# Nimb_Ring_2_0.net
KiCad netlist of a schematic drawn in Altium Designer
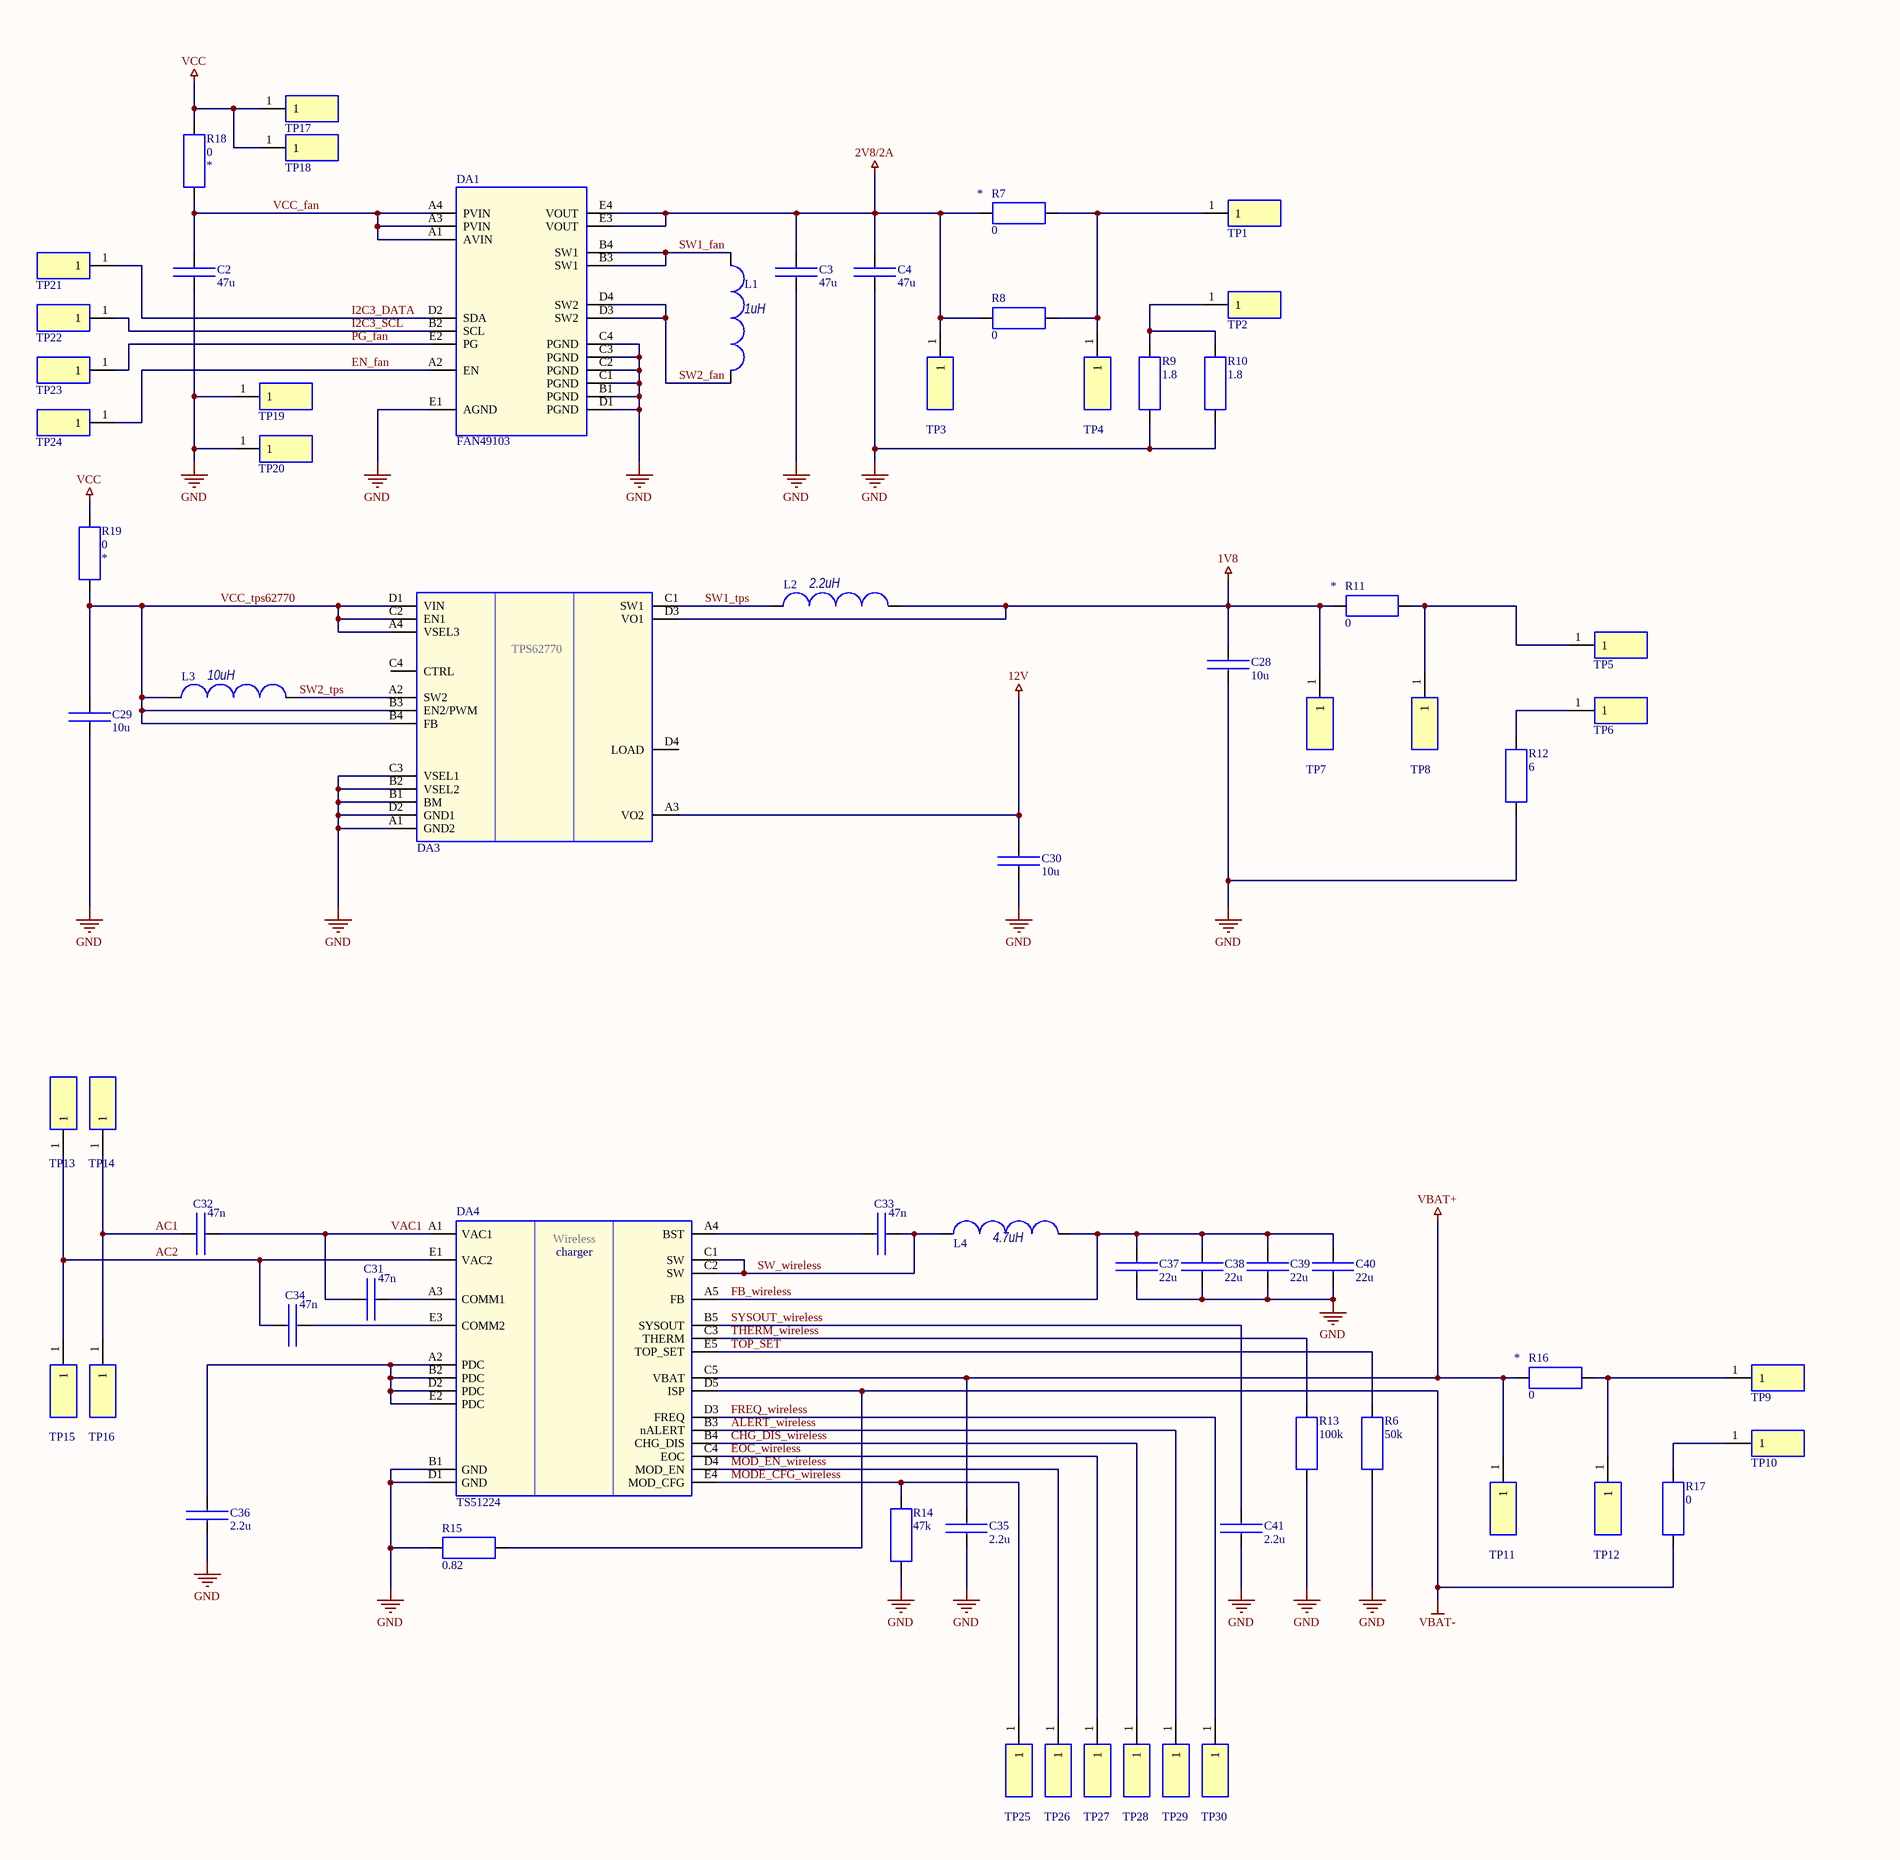
[diagram p0: Nimb_Ring_2_0.SchDoc, left]
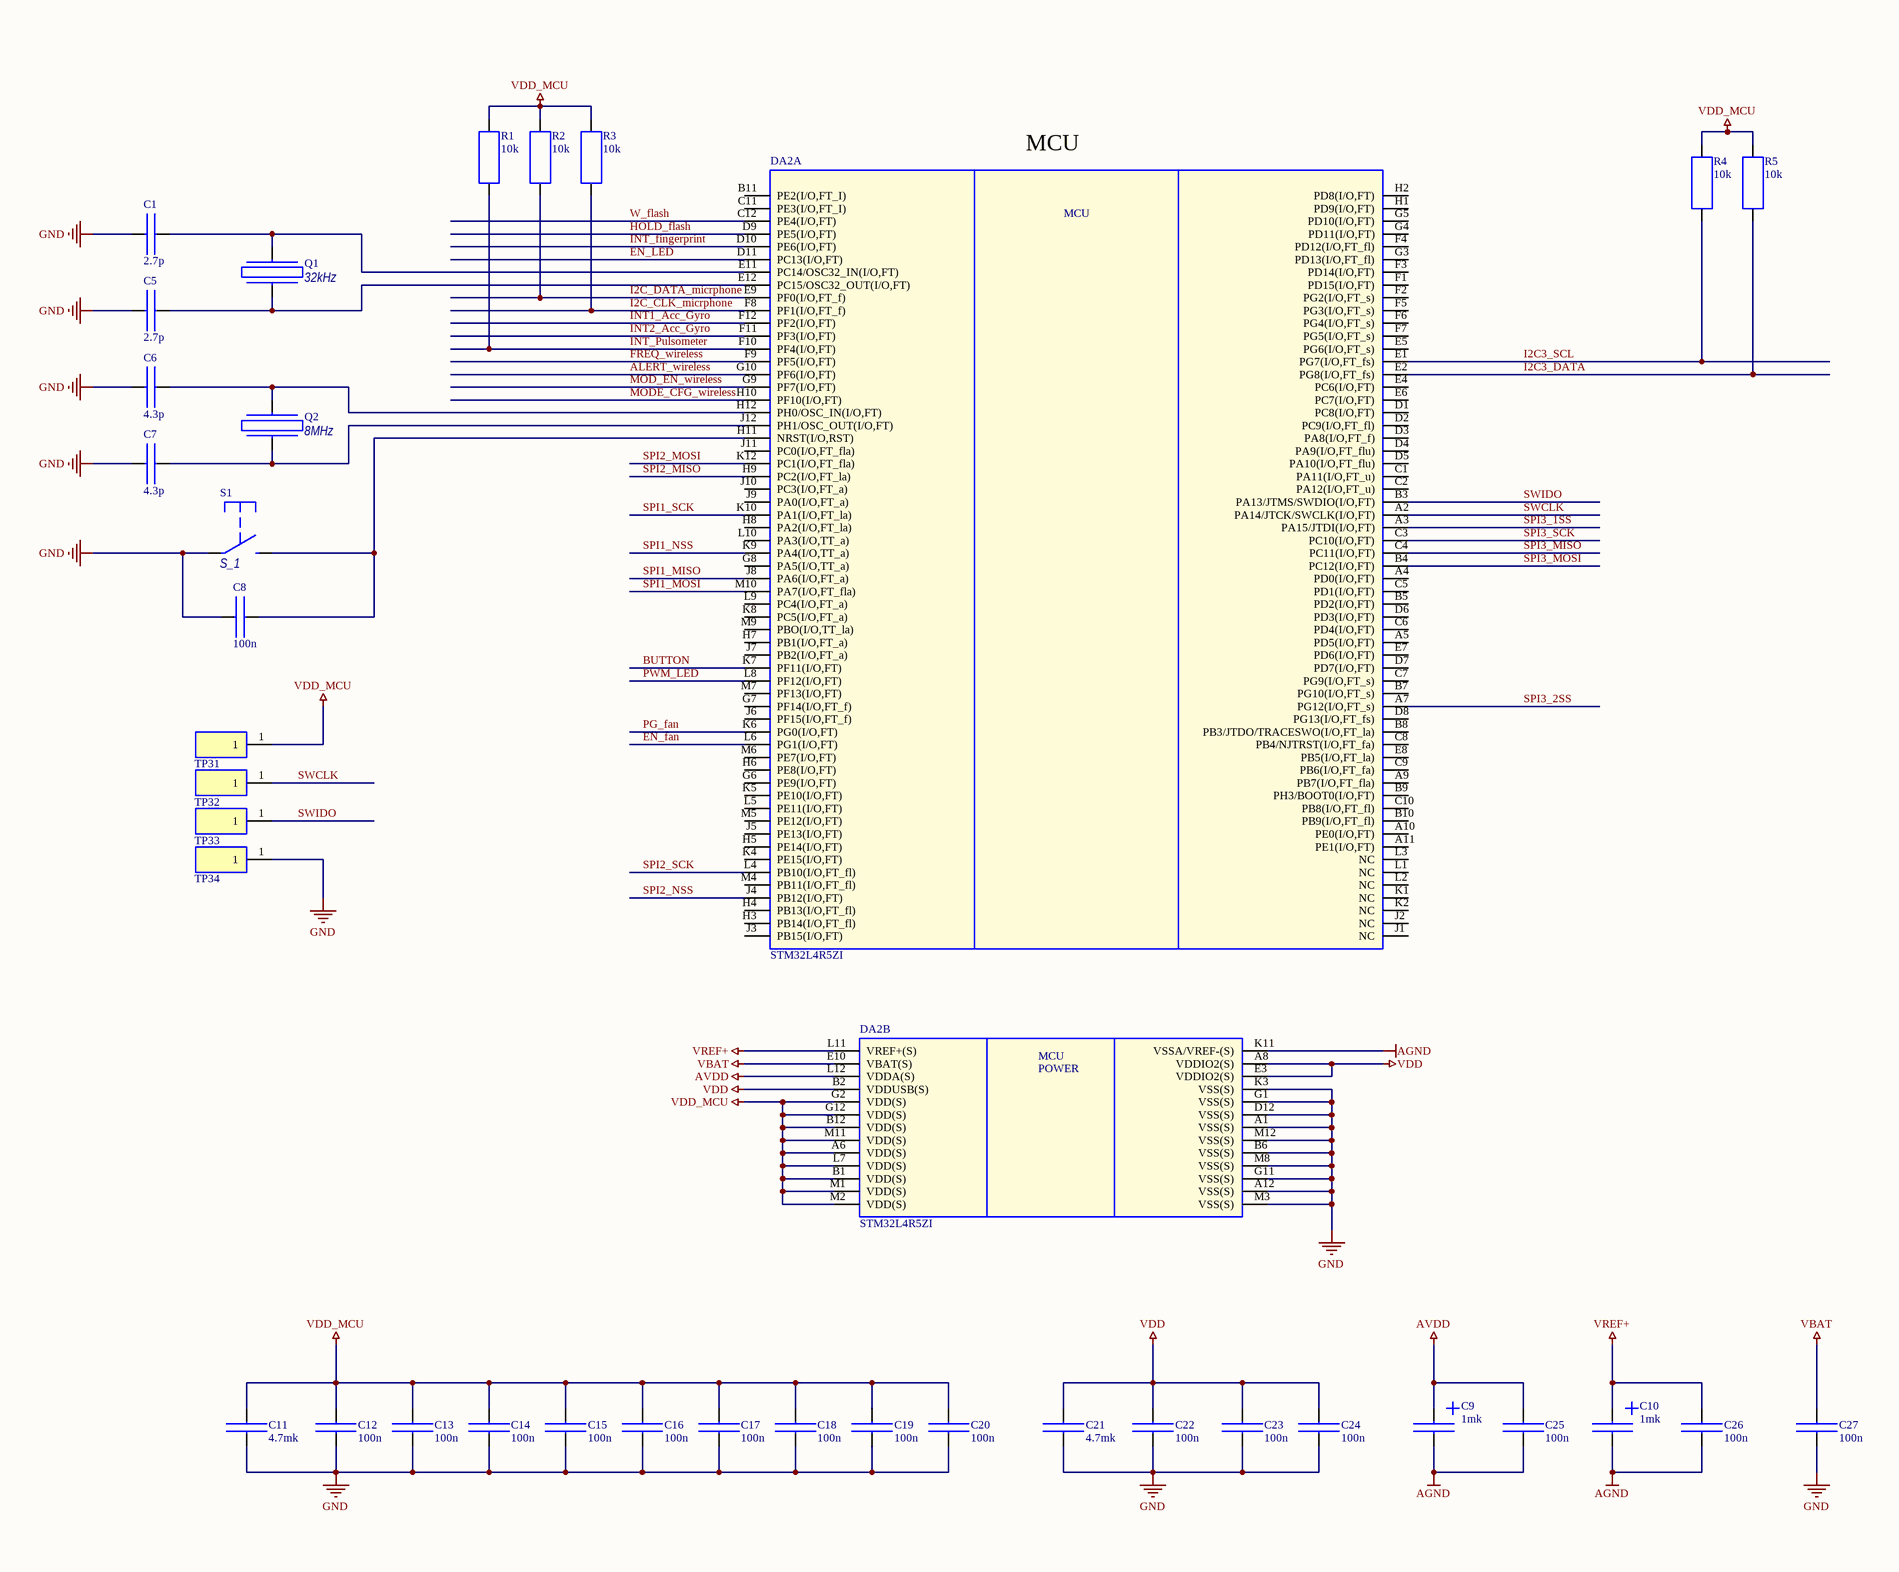
[diagram p1: Nimb_Ring_2_0.SchDoc, right]

(export (version "E")
  (design (tool "Eeschema 10.0.6"))
  (components
    (comp (ref "C1")
      (value "2.7p")
      (footprint "CAP_0201")
      (fields (field (name "MANUFACTURERPARTNUMBER") "GRM155R71C104KA88"))
      (libsource (lib "Altium_lib_Discrete") (part "C"))
    )
    (comp (ref "C2")
      (value "47u")
      (footprint "Cap0603")
      (description "CAP CER 47UF 6.3V X5R 0603")
      (fields (field (name "TOLERANCE") "20%") (field (name "MANUFACTURERPARTNUMBER") "GRM188R60J476ME15J"))
      (libsource (lib "Nimb_Ring") (part "C"))
    )
    (comp (ref "C3")
      (value "47u")
      (footprint "Cap0603")
      (description "CAP CER 47UF 6.3V X5R 0603")
      (fields (field (name "TOLERANCE") "20%") (field (name "MANUFACTURERPARTNUMBER") "GRM188R60J476ME15J"))
      (libsource (lib "Nimb_Ring") (part "C"))
    )
    (comp (ref "C4")
      (value "47u")
      (footprint "Cap0603")
      (description "CAP CER 47UF 6.3V X5R 0603")
      (fields (field (name "TOLERANCE") "20%") (field (name "MANUFACTURERPARTNUMBER") "GRM188R60J476ME15J"))
      (libsource (lib "Nimb_Ring") (part "C"))
    )
    (comp (ref "C5")
      (value "2.7p")
      (footprint "CAP_0201")
      (fields (field (name "MANUFACTURERPARTNUMBER") "GRM155R71C104KA88"))
      (libsource (lib "Altium_lib_Discrete") (part "C"))
    )
    (comp (ref "C6")
      (value "4.3p")
      (footprint "CAP_0201")
      (fields (field (name "MANUFACTURERPARTNUMBER") "GRM155R71C104KA88"))
      (libsource (lib "Altium_lib_Discrete") (part "C"))
    )
    (comp (ref "C7")
      (value "4.3p")
      (footprint "CAP_0201")
      (fields (field (name "MANUFACTURERPARTNUMBER") "GRM155R71C104KA88"))
      (libsource (lib "Altium_lib_Discrete") (part "C"))
    )
    (comp (ref "C8")
      (value "100n")
      (footprint "CAP_0201")
      (fields (field (name "MANUFACTURERPARTNUMBER") "GRM155R71C104KA88"))
      (libsource (lib "Altium_lib_Discrete") (part "C"))
    )
    (comp (ref "C9") (value "1mk") (footprint "CAP_0201") (libsource (lib "Nimb_Ring") (part "C_Polar")))
    (comp (ref "C10") (value "1mk") (footprint "CAP_0201") (libsource (lib "Nimb_Ring") (part "C_Polar")))
    (comp (ref "C11")
      (value "4.7mk")
      (footprint "CAP_0201")
      (libsource (lib "Altium_lib_Discrete") (part "C"))
    )
    (comp (ref "C12")
      (value "100n")
      (footprint "CAP_0201")
      (fields (field (name "MANUFACTURERPARTNUMBER") "GRM155R71C104KA88"))
      (libsource (lib "Altium_lib_Discrete") (part "C"))
    )
    (comp (ref "C13")
      (value "100n")
      (footprint "CAP_0201")
      (fields (field (name "MANUFACTURERPARTNUMBER") "GRM155R71C104KA88"))
      (libsource (lib "Altium_lib_Discrete") (part "C"))
    )
    (comp (ref "C14")
      (value "100n")
      (footprint "CAP_0201")
      (fields (field (name "MANUFACTURERPARTNUMBER") "GRM155R71C104KA88"))
      (libsource (lib "Altium_lib_Discrete") (part "C"))
    )
    (comp (ref "C15")
      (value "100n")
      (footprint "CAP_0201")
      (fields (field (name "MANUFACTURERPARTNUMBER") "GRM155R71C104KA88"))
      (libsource (lib "Altium_lib_Discrete") (part "C"))
    )
    (comp (ref "C16")
      (value "100n")
      (footprint "CAP_0201")
      (fields (field (name "MANUFACTURERPARTNUMBER") "GRM155R71C104KA88"))
      (libsource (lib "Altium_lib_Discrete") (part "C"))
    )
    (comp (ref "C17")
      (value "100n")
      (footprint "CAP_0201")
      (fields (field (name "MANUFACTURERPARTNUMBER") "GRM155R71C104KA88"))
      (libsource (lib "Altium_lib_Discrete") (part "C"))
    )
    (comp (ref "C18")
      (value "100n")
      (footprint "CAP_0201")
      (fields (field (name "MANUFACTURERPARTNUMBER") "GRM155R71C104KA88"))
      (libsource (lib "Altium_lib_Discrete") (part "C"))
    )
    (comp (ref "C19")
      (value "100n")
      (footprint "CAP_0201")
      (fields (field (name "MANUFACTURERPARTNUMBER") "GRM155R71C104KA88"))
      (libsource (lib "Altium_lib_Discrete") (part "C"))
    )
    (comp (ref "C20")
      (value "100n")
      (footprint "CAP_0201")
      (fields (field (name "MANUFACTURERPARTNUMBER") "GRM155R71C104KA88"))
      (libsource (lib "Altium_lib_Discrete") (part "C"))
    )
    (comp (ref "C21")
      (value "4.7mk")
      (footprint "CAP_0201")
      (libsource (lib "Altium_lib_Discrete") (part "C"))
    )
    (comp (ref "C22")
      (value "100n")
      (footprint "CAP_0201")
      (fields (field (name "MANUFACTURERPARTNUMBER") "GRM155R71C104KA88"))
      (libsource (lib "Altium_lib_Discrete") (part "C"))
    )
    (comp (ref "C23")
      (value "100n")
      (footprint "CAP_0201")
      (fields (field (name "MANUFACTURERPARTNUMBER") "GRM155R71C104KA88"))
      (libsource (lib "Altium_lib_Discrete") (part "C"))
    )
    (comp (ref "C24")
      (value "100n")
      (footprint "CAP_0201")
      (fields (field (name "MANUFACTURERPARTNUMBER") "GRM155R71C104KA88"))
      (libsource (lib "Altium_lib_Discrete") (part "C"))
    )
    (comp (ref "C25")
      (value "100n")
      (footprint "CAP_0201")
      (fields (field (name "MANUFACTURERPARTNUMBER") "GRM155R71C104KA88"))
      (libsource (lib "Altium_lib_Discrete") (part "C"))
    )
    (comp (ref "C26")
      (value "100n")
      (footprint "CAP_0201")
      (fields (field (name "MANUFACTURERPARTNUMBER") "GRM155R71C104KA88"))
      (libsource (lib "Altium_lib_Discrete") (part "C"))
    )
    (comp (ref "C27")
      (value "100n")
      (footprint "CAP_0201")
      (fields (field (name "MANUFACTURERPARTNUMBER") "GRM155R71C104KA88"))
      (libsource (lib "Altium_lib_Discrete") (part "C"))
    )
    (comp (ref "C28")
      (value "10u")
      (footprint "Cap0402")
      (description "CAP CER 10UF 6.3V X5R 0402")
      (fields (field (name "TOLERANCE") "20%") (field (name "MANUFACTURERPARTNUMBER") "GRM155R60J106ME44D"))
      (libsource (lib "Nimb_Ring") (part "C"))
    )
    (comp (ref "C29")
      (value "10u")
      (footprint "Cap0402")
      (description "CAP CER 10UF 6.3V X5R 0402")
      (fields (field (name "TOLERANCE") "20%") (field (name "MANUFACTURERPARTNUMBER") "GRM155R60J106ME44D"))
      (libsource (lib "Nimb_Ring") (part "C"))
    )
    (comp (ref "C30")
      (value "10u")
      (footprint "Cap0402")
      (description "CAP CER 10UF 6.3V X5R 0402")
      (fields (field (name "TOLERANCE") "20%") (field (name "MANUFACTURERPARTNUMBER") "GRM155R60J106ME44D"))
      (libsource (lib "Nimb_Ring") (part "C"))
    )
    (comp (ref "C31")
      (value "47n")
      (footprint "Cap0402")
      (description "CAP CER 47nF 50V X5R 0402")
      (fields (field (name "TOLERANCE") "10%") (field (name "MANUFACTURERPARTNUMBER") "GRM155R71H473KE14D"))
      (libsource (lib "Nimb_Ring") (part "C"))
    )
    (comp (ref "C32")
      (value "47n")
      (footprint "Cap0402")
      (description "CAP CER 47nF 50V X5R 0402")
      (fields (field (name "TOLERANCE") "10%") (field (name "MANUFACTURERPARTNUMBER") "GRM155R71H473KE14D"))
      (libsource (lib "Nimb_Ring") (part "C"))
    )
    (comp (ref "C33")
      (value "47n")
      (footprint "Cap0402")
      (description "CAP CER 47nF 10V X5R 0402")
      (fields (field (name "TOLERANCE") "10%") (field (name "MANUFACTURERPARTNUMBER") "GRM155R61A473KA01D"))
      (libsource (lib "Nimb_Ring") (part "C"))
    )
    (comp (ref "C34")
      (value "47n")
      (footprint "Cap0402")
      (description "CAP CER 47nF 50V X5R 0402")
      (fields (field (name "TOLERANCE") "10%") (field (name "MANUFACTURERPARTNUMBER") "GRM155R71H473KE14D"))
      (libsource (lib "Nimb_Ring") (part "C"))
    )
    (comp (ref "C35")
      (value "2.2u")
      (footprint "Cap0603")
      (description "CAP CER 2.2UF 10V X5R 0402")
      (fields (field (name "TOLERANCE") "10%") (field (name "MANUFACTURERPARTNUMBER") "GRM155R61A225KE95D"))
      (libsource (lib "Nimb_Ring") (part "C"))
    )
    (comp (ref "C36")
      (value "2.2u")
      (footprint "Cap0402")
      (description "CAP CER 2.2UF 25V X5R 0402")
      (fields (field (name "TOLERANCE") "10%") (field (name "MANUFACTURERPARTNUMBER") "GRM155R61E225KE11D"))
      (libsource (lib "Nimb_Ring") (part "C"))
    )
    (comp (ref "C37")
      (value "22u")
      (footprint "Cap0603")
      (description "CAP CER 22UF 10V X5R 0603")
      (fields (field (name "TOLERANCE") "15%") (field (name "MANUFACTURERPARTNUMBER") "ZRB18AR61A226ME01L"))
      (libsource (lib "Nimb_Ring") (part "C"))
    )
    (comp (ref "C38")
      (value "22u")
      (footprint "Cap0603")
      (description "CAP CER 22UF 10V X5R 0603")
      (fields (field (name "TOLERANCE") "15%") (field (name "MANUFACTURERPARTNUMBER") "ZRB18AR61A226ME01L"))
      (libsource (lib "Nimb_Ring") (part "C"))
    )
    (comp (ref "C39")
      (value "22u")
      (footprint "Cap0603")
      (description "CAP CER 22UF 10V X5R 0603")
      (fields (field (name "TOLERANCE") "15%") (field (name "MANUFACTURERPARTNUMBER") "ZRB18AR61A226ME01L"))
      (libsource (lib "Nimb_Ring") (part "C"))
    )
    (comp (ref "C40")
      (value "22u")
      (footprint "Cap0603")
      (description "CAP CER 22UF 10V X5R 0603")
      (fields (field (name "TOLERANCE") "15%") (field (name "MANUFACTURERPARTNUMBER") "ZRB18AR61A226ME01L"))
      (libsource (lib "Nimb_Ring") (part "C"))
    )
    (comp (ref "C41")
      (value "2.2u")
      (footprint "Cap0603")
      (description "CAP CER 2.2UF 10V X5R 0402")
      (fields (field (name "TOLERANCE") "10%") (field (name "MANUFACTURERPARTNUMBER") "GRM155R61A225KE95D"))
      (libsource (lib "Nimb_Ring") (part "C"))
    )
    (comp (ref "DA1")
      (value "FAN49103")
      (footprint "WLCSP20")
      (description "I2C Buck-Boost Regulator 2.5A")
      (fields (field (name "MANUFACTURER") "ON Semiconductor"))
      (libsource (lib "Nimb_Ring") (part "FAN49103"))
    )
    (comp (ref "DA2")
      (value "STM32L4R5ZI")
      (footprint "WLCSP144")
      (libsource (lib "Nimb_Ring") (part "STM32L4R5ZI"))
    )
    (comp (ref "DA3")
      (value "TPS62770")
      (footprint "DSBGA16")
      (description "Multi-Rail DC/DC Converter")
      (fields (field (name "MANUFACTURER") "Texas Instruments"))
      (libsource (lib "Nimb_Ring") (part "TPS62770"))
    )
    (comp (ref "DA4")
      (value "TS51224")
      (footprint "BGA_25 (5x5 ARRAY)")
      (description "IC RCVR CTLR WIRELESS 20-WLCSP")
      (fields (field (name "MANUFACTURER") "SEMTECH"))
      (libsource (lib "Nimb_Ring") (part "TS51224"))
    )
    (comp (ref "L1")
      (value "1uH")
      (footprint "Ind_0806")
      (description "FIXED IND 1UH 3.4A 0.048OHM")
      (fields (field (name "TOLERANCE") "20%") (field (name "MANUFACTURERPARTNUMBER") "DFE201612E1R0M"))
      (libsource (lib "Nimb_Ring") (part "L"))
    )
    (comp (ref "L2")
      (value "2.2uH")
      (footprint "IND_0806(2016metric)")
      (description "FIXED IND 2.2UH 1.2A 204mOHM")
      (fields (field (name "TOLERANCE") "20%") (field (name "MANUFACTURERPARTNUMBER") "1285AS-H-2R2M=P2"))
      (libsource (lib "Nimb_Ring") (part "L"))
    )
    (comp (ref "L3")
      (value "10uH")
      (footprint "IND_0806(2016metric)")
      (description "FIXED IND 10UH 225mA 1.2OHM")
      (fields (field (name "TOLERANCE") "10%") (field (name "MANUFACTURERPARTNUMBER") "LQH2MCN100K02L"))
      (libsource (lib "Nimb_Ring") (part "L"))
    )
    (comp (ref "L4")
      (value "4.7uH")
      (footprint "COIL-1008CS_V")
      (description "IND SMD 1008 4.7UH 1A 0.11OHM")
      (fields (field (name "TOLERANCE") "20%") (field (name "MANUFACTURERPARTNUMBER") "CVH252009-4R7M"))
      (libsource (lib "Nimb_Ring") (part "L"))
    )
    (comp (ref "Q1")
      (value "32kHz")
      (footprint "NX3215SA-32.768KHZ-EXS00A-MU00525")
      (libsource (lib "Altium_lib_Discrete") (part "Q_1"))
    )
    (comp (ref "Q2")
      (value "8MHz")
      (footprint "NDK-NX3225GD-8MHZ-STD-CRA-3_V")
      (libsource (lib "Altium_lib_Discrete") (part "Q_1"))
    )
    (comp (ref "R1") (value "10k") (footprint "RESC0402(1005)_L") (libsource (lib "Nimb_Ring") (part "R")))
    (comp (ref "R2") (value "10k") (footprint "RESC0402(1005)_L") (libsource (lib "Nimb_Ring") (part "R")))
    (comp (ref "R3") (value "10k") (footprint "RESC0402(1005)_L") (libsource (lib "Nimb_Ring") (part "R")))
    (comp (ref "R4") (value "10k") (footprint "RESC0402(1005)_L") (libsource (lib "Nimb_Ring") (part "R")))
    (comp (ref "R5") (value "10k") (footprint "RESC0402(1005)_L") (libsource (lib "Nimb_Ring") (part "R")))
    (comp (ref "R6")
      (value "50k")
      (footprint "RESC0402(1005)_L")
      (description "RES SMD 49.9kOHM 1% 62.5mW 0402")
      (fields (field (name "TOLERANCE") "1%") (field (name "MANUFACTURERPARTNUMBER") "RC0402FR-0749K9L"))
      (libsource (lib "Nimb_Ring") (part "R"))
    )
    (comp (ref "R7")
      (value "0")
      (footprint "RES2512(6332M)")
      (description "RES SMD 0 OHM 5% 1W 2512")
      (fields
        (field (name "TOLERANCE") "5%")
        (field (name "ПРИМЕЧАНИЕ") "*")
        (field (name "MANUFACTURERPARTNUMBER") "CR2512-J/-000ELF")
      )
      (libsource (lib "Nimb_Ring") (part "R"))
    )
    (comp (ref "R8")
      (value "0")
      (footprint "RES6.5-3.4X1.9")
      (description "Axial")
      (libsource (lib "Nimb_Ring") (part "R"))
    )
    (comp (ref "R9")
      (value "1.8")
      (footprint "RES2512(6332M)")
      (description "RES SMD 1.8OHM 5% 2W 2512")
      (fields
        (field (name "MANUFACTURERPARTNUMBER") "CRM2512-JW-1R8ELF")
        (field (name "MANUFACTURER") "Bourns")
      )
      (libsource (lib "Nimb_Ring") (part "R"))
    )
    (comp (ref "R10")
      (value "1.8")
      (footprint "RES6.5-3.4X1.9")
      (description "Axial")
      (libsource (lib "Nimb_Ring") (part "R"))
    )
    (comp (ref "R11")
      (value "0")
      (footprint "RES2512(6332M)")
      (description "RES SMD 0 OHM 5% 1W 2512")
      (fields
        (field (name "TOLERANCE") "5%")
        (field (name "ПРИМЕЧАНИЕ") "*")
        (field (name "MANUFACTURERPARTNUMBER") "CR2512-J/-000ELF")
      )
      (libsource (lib "Nimb_Ring") (part "R"))
    )
    (comp (ref "R12")
      (value "6")
      (footprint "RES2512(6332M)")
      (description "RES SMD 6OHM 5% 1W 2512")
      (fields (field (name "TOLERANCE") "1%") (field (name "MANUFACTURERPARTNUMBER") "RC2512FK-076R04L"))
      (libsource (lib "Nimb_Ring") (part "R"))
    )
    (comp (ref "R13")
      (value "100k")
      (footprint "RESC0402(1005)_L")
      (description "RES SMD 100kOHM 5% 62.5mW 0402")
      (fields (field (name "TOLERANCE") "5%") (field (name "MANUFACTURERPARTNUMBER") "RC0402JR-07100KL"))
      (libsource (lib "Nimb_Ring") (part "R"))
    )
    (comp (ref "R14")
      (value "47k")
      (footprint "RESC0402(1005)_L")
      (description "RES SMD 47kOHM 5% 62.5mW 0402")
      (fields (field (name "TOLERANCE") "5%") (field (name "MANUFACTURERPARTNUMBER") "RC0402JR-0747KL"))
      (libsource (lib "Nimb_Ring") (part "R"))
    )
    (comp (ref "R15")
      (value "0.82")
      (footprint "RES0603(1608M)")
      (description "RES SMD 0OHM 5% 1A 0603")
      (fields (field (name "TOLERANCE") "5%") (field (name "MANUFACTURERPARTNUMBER") "CRCW0603R820FSEABL"))
      (libsource (lib "Nimb_Ring") (part "R"))
    )
    (comp (ref "R16")
      (value "0")
      (footprint "RES2512(6332M)")
      (description "RES SMD 0 OHM 5% 1W 2512")
      (fields
        (field (name "TOLERANCE") "5%")
        (field (name "ПРИМЕЧАНИЕ") "*")
        (field (name "MANUFACTURERPARTNUMBER") "CR2512-J/-000ELF")
      )
      (libsource (lib "Nimb_Ring") (part "R"))
    )
    (comp (ref "R17") (value "0") (footprint "RES2512(6332M)") (libsource (lib "Nimb_Ring") (part "R")))
    (comp (ref "R18")
      (value "0")
      (footprint "RES2512(6332M)")
      (description "RES SMD 0 OHM 5% 1W 2512")
      (fields
        (field (name "TOLERANCE") "5%")
        (field (name "ПРИМЕЧАНИЕ") "*")
        (field (name "MANUFACTURERPARTNUMBER") "CR2512-J/-000ELF")
      )
      (libsource (lib "Nimb_Ring") (part "R"))
    )
    (comp (ref "R19")
      (value "0")
      (footprint "RES2512(6332M)")
      (description "RES SMD 0 OHM 5% 1W 2512")
      (fields
        (field (name "TOLERANCE") "5%")
        (field (name "ПРИМЕЧАНИЕ") "*")
        (field (name "MANUFACTURERPARTNUMBER") "CR2512-J/-000ELF")
      )
      (libsource (lib "Nimb_Ring") (part "R"))
    )
    (comp (ref "S1")
      (value "S_1")
      (footprint "BOUR-7914G-1-000E_V")
      (libsource (lib "Nimb_Ring") (part "S_1"))
    )
    (comp (ref "TP1")
      (value "Test_Pad")
      (footprint "TEST_PAD_Button")
      (libsource (lib "") (part "Test_Pad_1"))
    )
    (comp (ref "TP2")
      (value "Test_Pad")
      (footprint "TEST_PAD_Button")
      (libsource (lib "") (part "Test_Pad_1"))
    )
    (comp (ref "TP3") (value "Test_Pad") (footprint "Test_Pad_PLS1") (libsource (lib "") (part "Test_Pad_2")))
    (comp (ref "TP4") (value "Test_Pad") (footprint "Test_Pad_PLS1") (libsource (lib "") (part "Test_Pad_2")))
    (comp (ref "TP5")
      (value "Test_Pad")
      (footprint "TEST_PAD_Button")
      (libsource (lib "") (part "Test_Pad_1"))
    )
    (comp (ref "TP6")
      (value "Test_Pad")
      (footprint "TEST_PAD_Button")
      (libsource (lib "") (part "Test_Pad_1"))
    )
    (comp (ref "TP7") (value "Test_Pad") (footprint "Test_Pad_PLS1") (libsource (lib "") (part "Test_Pad_2")))
    (comp (ref "TP8") (value "Test_Pad") (footprint "Test_Pad_PLS1") (libsource (lib "") (part "Test_Pad_2")))
    (comp (ref "TP9")
      (value "Test_Pad")
      (footprint "TEST_PAD_Button")
      (libsource (lib "") (part "Test_Pad_1"))
    )
    (comp (ref "TP10")
      (value "Test_Pad")
      (footprint "TEST_PAD_Button")
      (libsource (lib "") (part "Test_Pad_1"))
    )
    (comp (ref "TP11")
      (value "Test_Pad")
      (footprint "Test_Pad_PLS1")
      (libsource (lib "") (part "Test_Pad_2"))
    )
    (comp (ref "TP12")
      (value "Test_Pad")
      (footprint "Test_Pad_PLS1")
      (libsource (lib "") (part "Test_Pad_2"))
    )
    (comp (ref "TP13")
      (value "Test_Pad")
      (footprint "Test_Pad_PLS1")
      (libsource (lib "") (part "Test_Pad_3"))
    )
    (comp (ref "TP14")
      (value "Test_Pad")
      (footprint "Test_Pad_PLS1")
      (libsource (lib "") (part "Test_Pad_3"))
    )
    (comp (ref "TP15")
      (value "Test_Pad")
      (footprint "TEST_PAD_Button")
      (libsource (lib "") (part "Test_Pad_2"))
    )
    (comp (ref "TP16")
      (value "Test_Pad")
      (footprint "TEST_PAD_Button")
      (libsource (lib "") (part "Test_Pad_2"))
    )
    (comp (ref "TP17")
      (value "Test_Pad")
      (footprint "TEST_PAD_Button")
      (libsource (lib "") (part "Test_Pad_1"))
    )
    (comp (ref "TP18")
      (value "Test_Pad")
      (footprint "Test_Pad_PLS1")
      (libsource (lib "") (part "Test_Pad_1"))
    )
    (comp (ref "TP19")
      (value "Test_Pad")
      (footprint "TEST_PAD_Button")
      (libsource (lib "") (part "Test_Pad_1"))
    )
    (comp (ref "TP20")
      (value "Test_Pad")
      (footprint "Test_Pad_PLS1")
      (libsource (lib "") (part "Test_Pad_1"))
    )
    (comp (ref "TP21")
      (value "Test_Pad")
      (footprint "Test_Pad_PLS1")
      (libsource (lib "Nimb_Ring") (part "Test_Pad"))
    )
    (comp (ref "TP22")
      (value "Test_Pad")
      (footprint "Test_Pad_PLS1")
      (libsource (lib "Nimb_Ring") (part "Test_Pad"))
    )
    (comp (ref "TP23")
      (value "Test_Pad")
      (footprint "Test_Pad_PLS1")
      (libsource (lib "Nimb_Ring") (part "Test_Pad"))
    )
    (comp (ref "TP24")
      (value "Test_Pad")
      (footprint "Test_Pad_PLS1")
      (libsource (lib "Nimb_Ring") (part "Test_Pad"))
    )
    (comp (ref "TP25")
      (value "Test_Pad")
      (footprint "Test_Pad_PLS1")
      (libsource (lib "") (part "Test_Pad_2"))
    )
    (comp (ref "TP26")
      (value "Test_Pad")
      (footprint "Test_Pad_PLS1")
      (libsource (lib "") (part "Test_Pad_2"))
    )
    (comp (ref "TP27")
      (value "Test_Pad")
      (footprint "Test_Pad_PLS1")
      (libsource (lib "") (part "Test_Pad_2"))
    )
    (comp (ref "TP28")
      (value "Test_Pad")
      (footprint "Test_Pad_PLS1")
      (libsource (lib "") (part "Test_Pad_2"))
    )
    (comp (ref "TP29")
      (value "Test_Pad")
      (footprint "Test_Pad_PLS1")
      (libsource (lib "") (part "Test_Pad_2"))
    )
    (comp (ref "TP30")
      (value "Test_Pad")
      (footprint "Test_Pad_PLS1")
      (libsource (lib "") (part "Test_Pad_2"))
    )
    (comp (ref "TP31")
      (value "Test_Pad")
      (footprint "Test_Pad_PLS1")
      (libsource (lib "Nimb_Ring") (part "Test_Pad"))
    )
    (comp (ref "TP32")
      (value "Test_Pad")
      (footprint "Test_Pad_PLS1")
      (libsource (lib "Nimb_Ring") (part "Test_Pad"))
    )
    (comp (ref "TP33")
      (value "Test_Pad")
      (footprint "Test_Pad_PLS1")
      (libsource (lib "Nimb_Ring") (part "Test_Pad"))
    )
    (comp (ref "TP34")
      (value "Test_Pad")
      (footprint "Test_Pad_PLS1")
      (libsource (lib "Nimb_Ring") (part "Test_Pad"))
    )
  )
  (nets
    (net (code "1") (name "/AC1") (class "Default")
      (node (ref "C32") (pin "1") (pintype "passive"))
      (node (ref "TP14") (pin "1") (pinfunction "1_1") (pintype "passive"))
      (node (ref "TP16") (pin "1") (pinfunction "1_1") (pintype "passive"))
    )
    (net (code "2") (name "/AC2") (class "Default")
      (node (ref "C34") (pin "1") (pintype "passive"))
      (node (ref "DA4") (pin "E1") (pinfunction "VAC2_E1") (pintype "passive"))
      (node (ref "TP13") (pin "1") (pinfunction "1_1") (pintype "passive"))
      (node (ref "TP15") (pin "1") (pinfunction "1_1") (pintype "passive"))
    )
    (net (code "3") (name "/ALERT_wireless") (class "Default")
      (node (ref "DA2") (pin "G10") (pinfunction "PF6(I/O,FT)_G10") (pintype "passive"))
      (node (ref "DA4") (pin "B3") (pinfunction "nALERT_B3") (pintype "passive"))
      (node (ref "TP29") (pin "1") (pinfunction "1_1") (pintype "passive"))
    )
    (net (code "4") (name "/BUTTON") (class "Default")
      (node (ref "DA2") (pin "K7") (pinfunction "PF11(I/O,FT)_K7") (pintype "passive"))
    )
    (net (code "5") (name "/CHG_DIS_wireless") (class "Default")
      (node (ref "DA4") (pin "B4") (pinfunction "CHG_DIS_B4") (pintype "passive"))
      (node (ref "TP28") (pin "1") (pinfunction "1_1") (pintype "passive"))
    )
    (net (code "6") (name "/EN_LED") (class "Default")
      (node (ref "DA2") (pin "D11") (pinfunction "PC13(I/O,FT)_D11") (pintype "passive"))
    )
    (net (code "7") (name "/EN_fan") (class "Default")
      (node (ref "DA1") (pin "A2") (pinfunction "EN_A2") (pintype "passive"))
      (node (ref "DA2") (pin "L6") (pinfunction "PG1(I/O,FT)_L6") (pintype "passive"))
      (node (ref "TP24") (pin "1") (pinfunction "1_1") (pintype "passive"))
    )
    (net (code "8") (name "/EOC_wireless") (class "Default")
      (node (ref "DA4") (pin "C4") (pinfunction "EOC_C4") (pintype "passive"))
      (node (ref "TP27") (pin "1") (pinfunction "1_1") (pintype "passive"))
    )
    (net (code "9") (name "/FB_wireless") (class "Default")
      (node (ref "C37") (pin "1") (pintype "passive"))
      (node (ref "C38") (pin "1") (pintype "passive"))
      (node (ref "C39") (pin "1") (pintype "passive"))
      (node (ref "C40") (pin "1") (pintype "passive"))
      (node (ref "DA4") (pin "A5") (pinfunction "FB_A5") (pintype "passive"))
      (node (ref "L4") (pin "2") (pintype "passive"))
    )
    (net (code "10") (name "/FREQ_wireless") (class "Default")
      (node (ref "DA2") (pin "F9") (pinfunction "PF5(I/O,FT)_F9") (pintype "passive"))
      (node (ref "DA4") (pin "D3") (pinfunction "FREQ_D3") (pintype "passive"))
      (node (ref "TP30") (pin "1") (pinfunction "1_1") (pintype "passive"))
    )
    (net (code "11") (name "/HOLD_flash") (class "Default")
      (node (ref "DA2") (pin "D9") (pinfunction "PE5(I/O,FT)_D9") (pintype "passive"))
    )
    (net (code "12") (name "/I2C3_DATA") (class "Default")
      (node (ref "DA1") (pin "D2") (pinfunction "SDA_D2") (pintype "passive"))
      (node (ref "DA2") (pin "E2") (pinfunction "PG8(I/O,FT_fs)_E2") (pintype "passive"))
      (node (ref "R5") (pin "1") (pintype "passive"))
      (node (ref "TP21") (pin "1") (pinfunction "1_1") (pintype "passive"))
    )
    (net (code "13") (name "/I2C3_SCL") (class "Default")
      (node (ref "DA1") (pin "B2") (pinfunction "SCL_B2") (pintype "passive"))
      (node (ref "DA2") (pin "E1") (pinfunction "PG7(I/O,FT_fs)_E1") (pintype "passive"))
      (node (ref "R4") (pin "1") (pintype "passive"))
      (node (ref "TP22") (pin "1") (pinfunction "1_1") (pintype "passive"))
    )
    (net (code "14") (name "/I2C_CLK_micrphone") (class "Default")
      (node (ref "DA2") (pin "F8") (pinfunction "PF1(I/O,FT_f)_F8") (pintype "passive"))
      (node (ref "R3") (pin "1") (pintype "passive"))
    )
    (net (code "15") (name "/I2C_DATA_micrphone") (class "Default")
      (node (ref "DA2") (pin "E9") (pinfunction "PF0(I/O,FT_f)_E9") (pintype "passive"))
      (node (ref "R2") (pin "1") (pintype "passive"))
    )
    (net (code "16") (name "/INT1_Acc_Gyro") (class "Default")
      (node (ref "DA2") (pin "F12") (pinfunction "PF2(I/O,FT)_F12") (pintype "passive"))
    )
    (net (code "17") (name "/INT2_Acc_Gyro") (class "Default")
      (node (ref "DA2") (pin "F11") (pinfunction "PF3(I/O,FT)_F11") (pintype "passive"))
    )
    (net (code "18") (name "/INT_Pulsometer") (class "Default")
      (node (ref "DA2") (pin "F10") (pinfunction "PF4(I/O,FT)_F10") (pintype "passive"))
      (node (ref "R1") (pin "1") (pintype "passive"))
    )
    (net (code "19") (name "/INT_fingerprint") (class "Default")
      (node (ref "DA2") (pin "D10") (pinfunction "PE6(I/O,FT)_D10") (pintype "passive"))
    )
    (net (code "20") (name "/MODE_CFG_wireless") (class "Default")
      (node (ref "DA2") (pin "H10") (pinfunction "PF10(I/O,FT)_H10") (pintype "passive"))
      (node (ref "DA4") (pin "E4") (pinfunction "MOD_CFG_E4") (pintype "passive"))
      (node (ref "R14") (pin "2") (pintype "passive"))
      (node (ref "TP25") (pin "1") (pinfunction "1_1") (pintype "passive"))
    )
    (net (code "21") (name "/MOD_EN_wireless") (class "Default")
      (node (ref "DA2") (pin "G9") (pinfunction "PF7(I/O,FT)_G9") (pintype "passive"))
      (node (ref "DA4") (pin "D4") (pinfunction "MOD_EN_D4") (pintype "passive"))
      (node (ref "TP26") (pin "1") (pinfunction "1_1") (pintype "passive"))
    )
    (net (code "22") (name "/PG_fan") (class "Default")
      (node (ref "DA1") (pin "E2") (pinfunction "PG_E2") (pintype "passive"))
      (node (ref "DA2") (pin "K6") (pinfunction "PG0(I/O,FT)_K6") (pintype "passive"))
      (node (ref "TP23") (pin "1") (pinfunction "1_1") (pintype "passive"))
    )
    (net (code "23") (name "/PWM_LED") (class "Default")
      (node (ref "DA2") (pin "L8") (pinfunction "PF12(I/O,FT)_L8") (pintype "passive"))
    )
    (net (code "24") (name "/SPI1_MISO") (class "Default")
      (node (ref "DA2") (pin "J8") (pinfunction "PA6(I/O,FT_a)_J8") (pintype "passive"))
    )
    (net (code "25") (name "/SPI1_MOSI") (class "Default")
      (node (ref "DA2") (pin "M10") (pinfunction "PA7(I/O,FT_fla)_M10") (pintype "passive"))
    )
    (net (code "26") (name "/SPI1_NSS") (class "Default")
      (node (ref "DA2") (pin "K9") (pinfunction "PA4(I/O,TT_a)_K9") (pintype "passive"))
    )
    (net (code "27") (name "/SPI1_SCK") (class "Default")
      (node (ref "DA2") (pin "K10") (pinfunction "PA1(I/O,FT_la)_K10") (pintype "passive"))
    )
    (net (code "28") (name "/SPI2_MISO") (class "Default")
      (node (ref "DA2") (pin "H9") (pinfunction "PC2(I/O,FT_la)_H9") (pintype "passive"))
    )
    (net (code "29") (name "/SPI2_MOSI") (class "Default")
      (node (ref "DA2") (pin "K12") (pinfunction "PC1(I/O,FT_fla)_K12") (pintype "passive"))
    )
    (net (code "30") (name "/SPI2_NSS") (class "Default")
      (node (ref "DA2") (pin "J4") (pinfunction "PB12(I/O,FT)_J4") (pintype "passive"))
    )
    (net (code "31") (name "/SPI2_SCK") (class "Default")
      (node (ref "DA2") (pin "L4") (pinfunction "PB10(I/O,FT_fl)_L4") (pintype "passive"))
    )
    (net (code "32") (name "/SPI3_1SS") (class "Default")
      (node (ref "DA2") (pin "A3") (pinfunction "PA15/JTDI(I/O,FT)_A3") (pintype "passive"))
    )
    (net (code "33") (name "/SPI3_2SS") (class "Default")
      (node (ref "DA2") (pin "A7") (pinfunction "PG12(I/O,FT_s)_A7") (pintype "passive"))
    )
    (net (code "34") (name "/SPI3_MISO") (class "Default")
      (node (ref "DA2") (pin "C4") (pinfunction "PC11(I/O,FT)_C4") (pintype "passive"))
    )
    (net (code "35") (name "/SPI3_MOSI") (class "Default")
      (node (ref "DA2") (pin "B4") (pinfunction "PC12(I/O,FT)_B4") (pintype "passive"))
    )
    (net (code "36") (name "/SPI3_SCK") (class "Default")
      (node (ref "DA2") (pin "C3") (pinfunction "PC10(I/O,FT)_C3") (pintype "passive"))
    )
    (net (code "37") (name "/SW1_fan") (class "Default")
      (node (ref "DA1") (pin "B3") (pinfunction "SW1_B3") (pintype "passive"))
      (node (ref "DA1") (pin "B4") (pinfunction "SW1_B4") (pintype "passive"))
      (node (ref "L1") (pin "1") (pintype "passive"))
    )
    (net (code "38") (name "/SW1_tps") (class "Default")
      (node (ref "DA3") (pin "C1") (pinfunction "SW1_C1") (pintype "passive"))
      (node (ref "L2") (pin "1") (pintype "passive"))
    )
    (net (code "39") (name "/SW2_fan") (class "Default")
      (node (ref "DA1") (pin "D3") (pinfunction "SW2_D3") (pintype "passive"))
      (node (ref "DA1") (pin "D4") (pinfunction "SW2_D4") (pintype "passive"))
      (node (ref "L1") (pin "2") (pintype "passive"))
    )
    (net (code "40") (name "/SW2_tps") (class "Default")
      (node (ref "DA3") (pin "A2") (pinfunction "SW2_A2") (pintype "passive"))
      (node (ref "L3") (pin "2") (pintype "passive"))
    )
    (net (code "41") (name "/SWCLK") (class "Default")
      (node (ref "DA2") (pin "A2") (pinfunction "PA14/JTCK/SWCLK(I/O,FT)_A2") (pintype "passive"))
      (node (ref "TP32") (pin "1") (pinfunction "1_1") (pintype "passive"))
    )
    (net (code "42") (name "/SWIDO") (class "Default")
      (node (ref "DA2") (pin "B3") (pinfunction "PA13/JTMS/SWDIO(I/O,FT)_B3") (pintype "passive"))
      (node (ref "TP33") (pin "1") (pinfunction "1_1") (pintype "passive"))
    )
    (net (code "43") (name "/SW_wireless") (class "Default")
      (node (ref "C33") (pin "1") (pintype "passive"))
      (node (ref "DA4") (pin "C1") (pinfunction "SW_C1") (pintype "passive"))
      (node (ref "DA4") (pin "C2") (pinfunction "SW_C2") (pintype "passive"))
      (node (ref "L4") (pin "1") (pintype "passive"))
    )
    (net (code "44") (name "/SYSOUT_wireless") (class "Default")
      (node (ref "C41") (pin "1") (pintype "passive"))
      (node (ref "DA4") (pin "B5") (pinfunction "SYSOUT_B5") (pintype "passive"))
    )
    (net (code "45") (name "/THERM_wireless") (class "Default")
      (node (ref "DA4") (pin "C3") (pinfunction "THERM_C3") (pintype "passive"))
      (node (ref "R13") (pin "2") (pintype "passive"))
    )
    (net (code "46") (name "/TOP_SET") (class "Default")
      (node (ref "DA4") (pin "E5") (pinfunction "TOP_SET_E5") (pintype "passive"))
      (node (ref "R6") (pin "2") (pintype "passive"))
    )
    (net (code "47") (name "/VAC1") (class "Default")
      (node (ref "C31") (pin "1") (pintype "passive"))
      (node (ref "C32") (pin "2") (pintype "passive"))
      (node (ref "DA4") (pin "A1") (pinfunction "VAC1_A1") (pintype "passive"))
    )
    (net (code "48") (name "/VCC_fan") (class "Default")
      (node (ref "C2") (pin "2") (pintype "passive"))
      (node (ref "DA1") (pin "A1") (pinfunction "AVIN_A1") (pintype "passive"))
      (node (ref "DA1") (pin "A3") (pinfunction "PVIN_A3") (pintype "passive"))
      (node (ref "DA1") (pin "A4") (pinfunction "PVIN_A4") (pintype "passive"))
      (node (ref "R18") (pin "2") (pintype "passive"))
    )
    (net (code "49") (name "/VCC_tps62770") (class "Default")
      (node (ref "C29") (pin "2") (pintype "passive"))
      (node (ref "DA3") (pin "A4") (pinfunction "VSEL3_A4") (pintype "passive"))
      (node (ref "DA3") (pin "B3") (pinfunction "EN2/PWM_B3") (pintype "passive"))
      (node (ref "DA3") (pin "B4") (pinfunction "FB_B4") (pintype "passive"))
      (node (ref "DA3") (pin "C2") (pinfunction "EN1_C2") (pintype "passive"))
      (node (ref "DA3") (pin "D1") (pinfunction "VIN_D1") (pintype "passive"))
      (node (ref "L3") (pin "1") (pintype "passive"))
      (node (ref "R19") (pin "2") (pintype "passive"))
    )
    (net (code "50") (name "/W_flash") (class "Default")
      (node (ref "DA2") (pin "C12") (pinfunction "PE4(I/O,FT)_C12") (pintype "passive"))
    )
    (net (code "51") (name "1V8") (class "Default")
      (node (ref "C28") (pin "2") (pintype "passive"))
      (node (ref "DA3") (pin "D3") (pinfunction "VO1_D3") (pintype "passive"))
      (node (ref "L2") (pin "2") (pintype "passive"))
      (node (ref "R11") (pin "2") (pintype "passive"))
      (node (ref "TP7") (pin "1") (pinfunction "1_1") (pintype "passive"))
    )
    (net (code "52") (name "2V8{slash}2A") (class "Default")
      (node (ref "C3") (pin "2") (pintype "passive"))
      (node (ref "C4") (pin "2") (pintype "passive"))
      (node (ref "DA1") (pin "E3") (pinfunction "VOUT_E3") (pintype "passive"))
      (node (ref "DA1") (pin "E4") (pinfunction "VOUT_E4") (pintype "passive"))
      (node (ref "R7") (pin "2") (pintype "passive"))
      (node (ref "R8") (pin "2") (pintype "passive"))
      (node (ref "TP3") (pin "1") (pinfunction "1_1") (pintype "passive"))
    )
    (net (code "53") (name "12V") (class "Default")
      (node (ref "C30") (pin "2") (pintype "passive"))
      (node (ref "DA3") (pin "A3") (pinfunction "VO2_A3") (pintype "passive"))
    )
    (net (code "54") (name "AGND") (class "Default")
      (node (ref "C10") (pin "2") (pintype "passive"))
      (node (ref "C25") (pin "1") (pintype "passive"))
      (node (ref "C26") (pin "1") (pintype "passive"))
      (node (ref "C9") (pin "2") (pintype "passive"))
      (node (ref "DA2") (pin "K11") (pinfunction "VSSA/VREF-(S)_K11") (pintype "passive"))
    )
    (net (code "55") (name "AVDD") (class "Default")
      (node (ref "C25") (pin "2") (pintype "passive"))
      (node (ref "C9") (pin "1") (pintype "passive"))
      (node (ref "DA2") (pin "L12") (pinfunction "VDDA(S)_L12") (pintype "passive"))
    )
    (net (code "56") (name "GND") (class "Default")
      (node (ref "C1") (pin "2") (pintype "passive"))
      (node (ref "C11") (pin "1") (pintype "passive"))
      (node (ref "C12") (pin "1") (pintype "passive"))
      (node (ref "C13") (pin "1") (pintype "passive"))
      (node (ref "C14") (pin "1") (pintype "passive"))
      (node (ref "C15") (pin "1") (pintype "passive"))
      (node (ref "C16") (pin "1") (pintype "passive"))
      (node (ref "C17") (pin "1") (pintype "passive"))
      (node (ref "C18") (pin "1") (pintype "passive"))
      (node (ref "C19") (pin "1") (pintype "passive"))
      (node (ref "C2") (pin "1") (pintype "passive"))
      (node (ref "C20") (pin "1") (pintype "passive"))
      (node (ref "C21") (pin "1") (pintype "passive"))
      (node (ref "C22") (pin "1") (pintype "passive"))
      (node (ref "C23") (pin "1") (pintype "passive"))
      (node (ref "C24") (pin "1") (pintype "passive"))
      (node (ref "C27") (pin "1") (pintype "passive"))
      (node (ref "C28") (pin "1") (pintype "passive"))
      (node (ref "C29") (pin "1") (pintype "passive"))
      (node (ref "C3") (pin "1") (pintype "passive"))
      (node (ref "C30") (pin "1") (pintype "passive"))
      (node (ref "C35") (pin "2") (pintype "passive"))
      (node (ref "C36") (pin "2") (pintype "passive"))
      (node (ref "C37") (pin "2") (pintype "passive"))
      (node (ref "C38") (pin "2") (pintype "passive"))
      (node (ref "C39") (pin "2") (pintype "passive"))
      (node (ref "C4") (pin "1") (pintype "passive"))
      (node (ref "C40") (pin "2") (pintype "passive"))
      (node (ref "C41") (pin "2") (pintype "passive"))
      (node (ref "C5") (pin "2") (pintype "passive"))
      (node (ref "C6") (pin "2") (pintype "passive"))
      (node (ref "C7") (pin "2") (pintype "passive"))
      (node (ref "C8") (pin "2") (pintype "passive"))
      (node (ref "DA1") (pin "B1") (pinfunction "PGND_B1") (pintype "passive"))
      (node (ref "DA1") (pin "C1") (pinfunction "PGND_C1") (pintype "passive"))
      (node (ref "DA1") (pin "C2") (pinfunction "PGND_C2") (pintype "passive"))
      (node (ref "DA1") (pin "C3") (pinfunction "PGND_C3") (pintype "passive"))
      (node (ref "DA1") (pin "C4") (pinfunction "PGND_C4") (pintype "passive"))
      (node (ref "DA1") (pin "D1") (pinfunction "PGND_D1") (pintype "passive"))
      (node (ref "DA1") (pin "E1") (pinfunction "AGND_E1") (pintype "passive"))
      (node (ref "DA2") (pin "A1") (pinfunction "VSS(S)_A1") (pintype "passive"))
      (node (ref "DA2") (pin "A12") (pinfunction "VSS(S)_A12") (pintype "passive"))
      (node (ref "DA2") (pin "B6") (pinfunction "VSS(S)_B6") (pintype "passive"))
      (node (ref "DA2") (pin "D12") (pinfunction "VSS(S)_D12") (pintype "passive"))
      (node (ref "DA2") (pin "G1") (pinfunction "VSS(S)_G1") (pintype "passive"))
      (node (ref "DA2") (pin "G11") (pinfunction "VSS(S)_G11") (pintype "passive"))
      (node (ref "DA2") (pin "K3") (pinfunction "VSS(S)_K3") (pintype "passive"))
      (node (ref "DA2") (pin "M12") (pinfunction "VSS(S)_M12") (pintype "passive"))
      (node (ref "DA2") (pin "M3") (pinfunction "VSS(S)_M3") (pintype "passive"))
      (node (ref "DA2") (pin "M8") (pinfunction "VSS(S)_M8") (pintype "passive"))
      (node (ref "DA3") (pin "A1") (pinfunction "GND2_A1") (pintype "passive"))
      (node (ref "DA3") (pin "B1") (pinfunction "BM_B1") (pintype "passive"))
      (node (ref "DA3") (pin "B2") (pinfunction "VSEL2_B2") (pintype "passive"))
      (node (ref "DA3") (pin "C3") (pinfunction "VSEL1_C3") (pintype "passive"))
      (node (ref "DA3") (pin "D2") (pinfunction "GND1_D2") (pintype "passive"))
      (node (ref "DA4") (pin "B1") (pinfunction "GND_B1") (pintype "passive"))
      (node (ref "DA4") (pin "D1") (pinfunction "GND_D1") (pintype "passive"))
      (node (ref "R10") (pin "2") (pintype "passive"))
      (node (ref "R12") (pin "2") (pintype "passive"))
      (node (ref "R13") (pin "1") (pintype "passive"))
      (node (ref "R14") (pin "1") (pintype "passive"))
      (node (ref "R15") (pin "2") (pintype "passive"))
      (node (ref "R6") (pin "1") (pintype "passive"))
      (node (ref "R9") (pin "2") (pintype "passive"))
      (node (ref "S1") (pin "1") (pintype "passive"))
      (node (ref "TP19") (pin "1") (pinfunction "1_1") (pintype "passive"))
      (node (ref "TP20") (pin "1") (pinfunction "1_1") (pintype "passive"))
      (node (ref "TP34") (pin "1") (pinfunction "1_1") (pintype "passive"))
    )
    (net (code "57") (name "Net-(C36-Pad1)") (class "Default")
      (node (ref "C36") (pin "1") (pintype "passive"))
      (node (ref "DA4") (pin "A2") (pinfunction "PDC_A2") (pintype "passive"))
      (node (ref "DA4") (pin "B2") (pinfunction "PDC_B2") (pintype "passive"))
      (node (ref "DA4") (pin "D2") (pinfunction "PDC_D2") (pintype "passive"))
      (node (ref "DA4") (pin "E2") (pinfunction "PDC_E2") (pintype "passive"))
    )
    (net (code "58") (name "Net-(DA2A-NRST(I{slash}O,RST))") (class "Default")
      (node (ref "C8") (pin "1") (pintype "passive"))
      (node (ref "DA2") (pin "H11") (pinfunction "NRST(I/O,RST)_H11") (pintype "passive"))
      (node (ref "S1") (pin "2") (pintype "passive"))
    )
    (net (code "59") (name "Net-(DA2A-PC14{slash}OSC32_IN(I{slash}O,FT))") (class "Default")
      (node (ref "C1") (pin "1") (pintype "passive"))
      (node (ref "DA2") (pin "E11") (pinfunction "PC14/OSC32_IN(I/O,FT)_E11") (pintype "passive"))
      (node (ref "Q1") (pin "1") (pintype "passive"))
    )
    (net (code "60") (name "Net-(DA2A-PC15{slash}OSC32_OUT(I{slash}O,FT))") (class "Default")
      (node (ref "C5") (pin "1") (pintype "passive"))
      (node (ref "DA2") (pin "E12") (pinfunction "PC15/OSC32_OUT(I/O,FT)_E12") (pintype "passive"))
      (node (ref "Q1") (pin "2") (pintype "passive"))
    )
    (net (code "61") (name "Net-(DA2A-PH0{slash}OSC_IN(I{slash}O,FT))") (class "Default")
      (node (ref "C6") (pin "1") (pintype "passive"))
      (node (ref "DA2") (pin "H12") (pinfunction "PH0/OSC_IN(I/O,FT)_H12") (pintype "passive"))
      (node (ref "Q2") (pin "1") (pintype "passive"))
    )
    (net (code "62") (name "Net-(DA2A-PH1{slash}OSC_OUT(I{slash}O,FT))") (class "Default")
      (node (ref "C7") (pin "1") (pintype "passive"))
      (node (ref "DA2") (pin "J12") (pinfunction "PH1/OSC_OUT(I/O,FT)_J12") (pintype "passive"))
      (node (ref "Q2") (pin "2") (pintype "passive"))
    )
    (net (code "63") (name "Net-(DA4-BST)") (class "Default")
      (node (ref "C33") (pin "2") (pintype "passive"))
      (node (ref "DA4") (pin "A4") (pinfunction "BST_A4") (pintype "passive"))
    )
    (net (code "64") (name "Net-(DA4-COMM1)") (class "Default")
      (node (ref "C31") (pin "2") (pintype "passive"))
      (node (ref "DA4") (pin "A3") (pinfunction "COMM1_A3") (pintype "passive"))
    )
    (net (code "65") (name "Net-(DA4-COMM2)") (class "Default")
      (node (ref "C34") (pin "2") (pintype "passive"))
      (node (ref "DA4") (pin "E3") (pinfunction "COMM2_E3") (pintype "passive"))
    )
    (net (code "66") (name "Net-(R7-Pad1)") (class "Default")
      (node (ref "R7") (pin "1") (pintype "passive"))
      (node (ref "R8") (pin "1") (pintype "passive"))
      (node (ref "TP1") (pin "1") (pinfunction "1_1") (pintype "passive"))
      (node (ref "TP4") (pin "1") (pinfunction "1_1") (pintype "passive"))
    )
    (net (code "67") (name "Net-(R10-Pad1)") (class "Default")
      (node (ref "R10") (pin "1") (pintype "passive"))
      (node (ref "R9") (pin "1") (pintype "passive"))
      (node (ref "TP2") (pin "1") (pinfunction "1_1") (pintype "passive"))
    )
    (net (code "68") (name "Net-(R11-Pad1)") (class "Default")
      (node (ref "R11") (pin "1") (pintype "passive"))
      (node (ref "TP5") (pin "1") (pinfunction "1_1") (pintype "passive"))
      (node (ref "TP8") (pin "1") (pinfunction "1_1") (pintype "passive"))
    )
    (net (code "69") (name "Net-(R12-Pad1)") (class "Default")
      (node (ref "R12") (pin "1") (pintype "passive"))
      (node (ref "TP6") (pin "1") (pinfunction "1_1") (pintype "passive"))
    )
    (net (code "70") (name "Net-(R16-Pad1)") (class "Default")
      (node (ref "R16") (pin "1") (pintype "passive"))
      (node (ref "TP12") (pin "1") (pinfunction "1_1") (pintype "passive"))
      (node (ref "TP9") (pin "1") (pinfunction "1_1") (pintype "passive"))
    )
    (net (code "71") (name "Net-(R17-Pad1)") (class "Default")
      (node (ref "R17") (pin "1") (pintype "passive"))
      (node (ref "TP10") (pin "1") (pinfunction "1_1") (pintype "passive"))
    )
    (net (code "72") (name "VBAT") (class "Default")
      (node (ref "C27") (pin "2") (pintype "passive"))
      (node (ref "DA2") (pin "E10") (pinfunction "VBAT(S)_E10") (pintype "passive"))
    )
    (net (code "73") (name "VBAT+") (class "Default")
      (node (ref "C35") (pin "1") (pintype "passive"))
      (node (ref "DA4") (pin "C5") (pinfunction "VBAT_C5") (pintype "passive"))
      (node (ref "R16") (pin "2") (pintype "passive"))
      (node (ref "TP11") (pin "1") (pinfunction "1_1") (pintype "passive"))
    )
    (net (code "74") (name "VBAT-") (class "Default")
      (node (ref "DA4") (pin "D5") (pinfunction "ISP_D5") (pintype "passive"))
      (node (ref "R15") (pin "1") (pintype "passive"))
      (node (ref "R17") (pin "2") (pintype "passive"))
    )
    (net (code "75") (name "VCC") (class "Default")
      (node (ref "R18") (pin "1") (pintype "passive"))
      (node (ref "R19") (pin "1") (pintype "passive"))
      (node (ref "TP17") (pin "1") (pinfunction "1_1") (pintype "passive"))
      (node (ref "TP18") (pin "1") (pinfunction "1_1") (pintype "passive"))
    )
    (net (code "76") (name "VDD") (class "Default")
      (node (ref "C21") (pin "2") (pintype "passive"))
      (node (ref "C22") (pin "2") (pintype "passive"))
      (node (ref "C23") (pin "2") (pintype "passive"))
      (node (ref "C24") (pin "2") (pintype "passive"))
      (node (ref "DA2") (pin "A8") (pinfunction "VDDIO2(S)_A8") (pintype "passive"))
      (node (ref "DA2") (pin "B2") (pinfunction "VDDUSB(S)_B2") (pintype "passive"))
      (node (ref "DA2") (pin "E3") (pinfunction "VDDIO2(S)_E3") (pintype "passive"))
    )
    (net (code "77") (name "VDD_MCU") (class "Default")
      (node (ref "C11") (pin "2") (pintype "passive"))
      (node (ref "C12") (pin "2") (pintype "passive"))
      (node (ref "C13") (pin "2") (pintype "passive"))
      (node (ref "C14") (pin "2") (pintype "passive"))
      (node (ref "C15") (pin "2") (pintype "passive"))
      (node (ref "C16") (pin "2") (pintype "passive"))
      (node (ref "C17") (pin "2") (pintype "passive"))
      (node (ref "C18") (pin "2") (pintype "passive"))
      (node (ref "C19") (pin "2") (pintype "passive"))
      (node (ref "C20") (pin "2") (pintype "passive"))
      (node (ref "DA2") (pin "A6") (pinfunction "VDD(S)_A6") (pintype "passive"))
      (node (ref "DA2") (pin "B1") (pinfunction "VDD(S)_B1") (pintype "passive"))
      (node (ref "DA2") (pin "B12") (pinfunction "VDD(S)_B12") (pintype "passive"))
      (node (ref "DA2") (pin "G12") (pinfunction "VDD(S)_G12") (pintype "passive"))
      (node (ref "DA2") (pin "G2") (pinfunction "VDD(S)_G2") (pintype "passive"))
      (node (ref "DA2") (pin "L7") (pinfunction "VDD(S)_L7") (pintype "passive"))
      (node (ref "DA2") (pin "M1") (pinfunction "VDD(S)_M1") (pintype "passive"))
      (node (ref "DA2") (pin "M11") (pinfunction "VDD(S)_M11") (pintype "passive"))
      (node (ref "DA2") (pin "M2") (pinfunction "VDD(S)_M2") (pintype "passive"))
      (node (ref "R1") (pin "2") (pintype "passive"))
      (node (ref "R2") (pin "2") (pintype "passive"))
      (node (ref "R3") (pin "2") (pintype "passive"))
      (node (ref "R4") (pin "2") (pintype "passive"))
      (node (ref "R5") (pin "2") (pintype "passive"))
      (node (ref "TP31") (pin "1") (pinfunction "1_1") (pintype "passive"))
    )
    (net (code "78") (name "VREF+") (class "Default")
      (node (ref "C10") (pin "1") (pintype "passive"))
      (node (ref "C26") (pin "2") (pintype "passive"))
      (node (ref "DA2") (pin "L11") (pinfunction "VREF+(S)_L11") (pintype "passive"))
    )
    (net (code "79") (name "unconnected-(DA2A-NC-PadJ1)") (class "Default")
      (node (ref "DA2") (pin "J1") (pinfunction "NC_J1") (pintype "passive"))
    )
    (net (code "80") (name "unconnected-(DA2A-NC-PadJ2)") (class "Default")
      (node (ref "DA2") (pin "J2") (pinfunction "NC_J2") (pintype "passive"))
    )
    (net (code "81") (name "unconnected-(DA2A-NC-PadK1)") (class "Default")
      (node (ref "DA2") (pin "K1") (pinfunction "NC_K1") (pintype "passive"))
    )
    (net (code "82") (name "unconnected-(DA2A-NC-PadK2)") (class "Default")
      (node (ref "DA2") (pin "K2") (pinfunction "NC_K2") (pintype "passive"))
    )
    (net (code "83") (name "unconnected-(DA2A-NC-PadL1)") (class "Default")
      (node (ref "DA2") (pin "L1") (pinfunction "NC_L1") (pintype "passive"))
    )
    (net (code "84") (name "unconnected-(DA2A-NC-PadL2)") (class "Default")
      (node (ref "DA2") (pin "L2") (pinfunction "NC_L2") (pintype "passive"))
    )
    (net (code "85") (name "unconnected-(DA2A-NC-PadL3)") (class "Default")
      (node (ref "DA2") (pin "L3") (pinfunction "NC_L3") (pintype "passive"))
    )
    (net (code "86") (name "unconnected-(DA2A-PA0(I{slash}O,FT_a)-PadJ9)") (class "Default")
      (node (ref "DA2") (pin "J9") (pinfunction "PA0(I/O,FT_a)_J9") (pintype "passive"))
    )
    (net (code "87") (name "unconnected-(DA2A-PA2(I{slash}O,FT_la)-PadH8)") (class "Default")
      (node (ref "DA2") (pin "H8") (pinfunction "PA2(I/O,FT_la)_H8") (pintype "passive"))
    )
    (net (code "88") (name "unconnected-(DA2A-PA3(I{slash}O,TT_a)-PadL10)") (class "Default")
      (node (ref "DA2") (pin "L10") (pinfunction "PA3(I/O,TT_a)_L10") (pintype "passive"))
    )
    (net (code "89") (name "unconnected-(DA2A-PA5(I{slash}O,TT_a)-PadG8)") (class "Default")
      (node (ref "DA2") (pin "G8") (pinfunction "PA5(I/O,TT_a)_G8") (pintype "passive"))
    )
    (net (code "90") (name "unconnected-(DA2A-PA8(I{slash}O,FT_f)-PadD3)") (class "Default")
      (node (ref "DA2") (pin "D3") (pinfunction "PA8(I/O,FT_f)_D3") (pintype "passive"))
    )
    (net (code "91") (name "unconnected-(DA2A-PA9(I{slash}O,FT_flu)-PadD4)") (class "Default")
      (node (ref "DA2") (pin "D4") (pinfunction "PA9(I/O,FT_flu)_D4") (pintype "passive"))
    )
    (net (code "92") (name "unconnected-(DA2A-PA10(I{slash}O,FT_flu)-PadD5)") (class "Default")
      (node (ref "DA2") (pin "D5") (pinfunction "PA10(I/O,FT_flu)_D5") (pintype "passive"))
    )
    (net (code "93") (name "unconnected-(DA2A-PA11(I{slash}O,FT_u)-PadC1)") (class "Default")
      (node (ref "DA2") (pin "C1") (pinfunction "PA11(I/O,FT_u)_C1") (pintype "passive"))
    )
    (net (code "94") (name "unconnected-(DA2A-PA12(I{slash}O,FT_u)-PadC2)") (class "Default")
      (node (ref "DA2") (pin "C2") (pinfunction "PA12(I/O,FT_u)_C2") (pintype "passive"))
    )
    (net (code "95") (name "unconnected-(DA2A-PB1(I{slash}O,FT_a)-PadH7)") (class "Default")
      (node (ref "DA2") (pin "H7") (pinfunction "PB1(I/O,FT_a)_H7") (pintype "passive"))
    )
    (net (code "96") (name "unconnected-(DA2A-PB2(I{slash}O,FT_a)-PadJ7)") (class "Default")
      (node (ref "DA2") (pin "J7") (pinfunction "PB2(I/O,FT_a)_J7") (pintype "passive"))
    )
    (net (code "97") (name "unconnected-(DA2A-PB3{slash}JTDO{slash}TRACESWO(I{slash}O,FT_la)-PadB8)") (class "Default")
      (node (ref "DA2") (pin "B8") (pinfunction "PB3/JTDO/TRACESWO(I/O,FT_la)_B8") (pintype "passive"))
    )
    (net (code "98") (name "unconnected-(DA2A-PB4{slash}NJTRST(I{slash}O,FT_fa)-PadC8)") (class "Default")
      (node (ref "DA2") (pin "C8") (pinfunction "PB4/NJTRST(I/O,FT_fa)_C8") (pintype "passive"))
    )
    (net (code "99") (name "unconnected-(DA2A-PB5(I{slash}O,FT_la)-PadE8)") (class "Default")
      (node (ref "DA2") (pin "E8") (pinfunction "PB5(I/O,FT_la)_E8") (pintype "passive"))
    )
    (net (code "100") (name "unconnected-(DA2A-PB6(I{slash}O,FT_fa)-PadC9)") (class "Default")
      (node (ref "DA2") (pin "C9") (pinfunction "PB6(I/O,FT_fa)_C9") (pintype "passive"))
    )
    (net (code "101") (name "unconnected-(DA2A-PB7(I{slash}O,FT_fla)-PadA9)") (class "Default")
      (node (ref "DA2") (pin "A9") (pinfunction "PB7(I/O,FT_fla)_A9") (pintype "passive"))
    )
    (net (code "102") (name "unconnected-(DA2A-PB8(I{slash}O,FT_fl)-PadC10)") (class "Default")
      (node (ref "DA2") (pin "C10") (pinfunction "PB8(I/O,FT_fl)_C10") (pintype "passive"))
    )
    (net (code "103") (name "unconnected-(DA2A-PB9(I{slash}O,FT_fl)-PadB10)") (class "Default")
      (node (ref "DA2") (pin "B10") (pinfunction "PB9(I/O,FT_fl)_B10") (pintype "passive"))
    )
    (net (code "104") (name "unconnected-(DA2A-PB11(I{slash}O,FT_fl)-PadM4)") (class "Default")
      (node (ref "DA2") (pin "M4") (pinfunction "PB11(I/O,FT_fl)_M4") (pintype "passive"))
    )
    (net (code "105") (name "unconnected-(DA2A-PB13(I{slash}O,FT_fl)-PadH4)") (class "Default")
      (node (ref "DA2") (pin "H4") (pinfunction "PB13(I/O,FT_fl)_H4") (pintype "passive"))
    )
    (net (code "106") (name "unconnected-(DA2A-PB14(I{slash}O,FT_fl)-PadH3)") (class "Default")
      (node (ref "DA2") (pin "H3") (pinfunction "PB14(I/O,FT_fl)_H3") (pintype "passive"))
    )
    (net (code "107") (name "unconnected-(DA2A-PB15(I{slash}O,FT)-PadJ3)") (class "Default")
      (node (ref "DA2") (pin "J3") (pinfunction "PB15(I/O,FT)_J3") (pintype "passive"))
    )
    (net (code "108") (name "unconnected-(DA2A-PBO(I{slash}O,TT_la)-PadM9)") (class "Default")
      (node (ref "DA2") (pin "M9") (pinfunction "PBO(I/O,TT_la)_M9") (pintype "passive"))
    )
    (net (code "109") (name "unconnected-(DA2A-PC0(I{slash}O,FT_fla)-PadJ11)") (class "Default")
      (node (ref "DA2") (pin "J11") (pinfunction "PC0(I/O,FT_fla)_J11") (pintype "passive"))
    )
    (net (code "110") (name "unconnected-(DA2A-PC3(I{slash}O,FT_a)-PadJ10)") (class "Default")
      (node (ref "DA2") (pin "J10") (pinfunction "PC3(I/O,FT_a)_J10") (pintype "passive"))
    )
    (net (code "111") (name "unconnected-(DA2A-PC4(I{slash}O,FT_a)-PadL9)") (class "Default")
      (node (ref "DA2") (pin "L9") (pinfunction "PC4(I/O,FT_a)_L9") (pintype "passive"))
    )
    (net (code "112") (name "unconnected-(DA2A-PC5(I{slash}O,FT_a)-PadK8)") (class "Default")
      (node (ref "DA2") (pin "K8") (pinfunction "PC5(I/O,FT_a)_K8") (pintype "passive"))
    )
    (net (code "113") (name "unconnected-(DA2A-PC6(I{slash}O,FT)-PadE4)") (class "Default")
      (node (ref "DA2") (pin "E4") (pinfunction "PC6(I/O,FT)_E4") (pintype "passive"))
    )
    (net (code "114") (name "unconnected-(DA2A-PC7(I{slash}O,FT)-PadE6)") (class "Default")
      (node (ref "DA2") (pin "E6") (pinfunction "PC7(I/O,FT)_E6") (pintype "passive"))
    )
    (net (code "115") (name "unconnected-(DA2A-PC8(I{slash}O,FT)-PadD1)") (class "Default")
      (node (ref "DA2") (pin "D1") (pinfunction "PC8(I/O,FT)_D1") (pintype "passive"))
    )
    (net (code "116") (name "unconnected-(DA2A-PC9(I{slash}O,FT_fl)-PadD2)") (class "Default")
      (node (ref "DA2") (pin "D2") (pinfunction "PC9(I/O,FT_fl)_D2") (pintype "passive"))
    )
    (net (code "117") (name "unconnected-(DA2A-PD0(I{slash}O,FT)-PadA4)") (class "Default")
      (node (ref "DA2") (pin "A4") (pinfunction "PD0(I/O,FT)_A4") (pintype "passive"))
    )
    (net (code "118") (name "unconnected-(DA2A-PD1(I{slash}O,FT)-PadC5)") (class "Default")
      (node (ref "DA2") (pin "C5") (pinfunction "PD1(I/O,FT)_C5") (pintype "passive"))
    )
    (net (code "119") (name "unconnected-(DA2A-PD2(I{slash}O,FT)-PadB5)") (class "Default")
      (node (ref "DA2") (pin "B5") (pinfunction "PD2(I/O,FT)_B5") (pintype "passive"))
    )
    (net (code "120") (name "unconnected-(DA2A-PD3(I{slash}O,FT)-PadD6)") (class "Default")
      (node (ref "DA2") (pin "D6") (pinfunction "PD3(I/O,FT)_D6") (pintype "passive"))
    )
    (net (code "121") (name "unconnected-(DA2A-PD4(I{slash}O,FT)-PadC6)") (class "Default")
      (node (ref "DA2") (pin "C6") (pinfunction "PD4(I/O,FT)_C6") (pintype "passive"))
    )
    (net (code "122") (name "unconnected-(DA2A-PD5(I{slash}O,FT)-PadA5)") (class "Default")
      (node (ref "DA2") (pin "A5") (pinfunction "PD5(I/O,FT)_A5") (pintype "passive"))
    )
    (net (code "123") (name "unconnected-(DA2A-PD6(I{slash}O,FT)-PadE7)") (class "Default")
      (node (ref "DA2") (pin "E7") (pinfunction "PD6(I/O,FT)_E7") (pintype "passive"))
    )
    (net (code "124") (name "unconnected-(DA2A-PD7(I{slash}O,FT)-PadD7)") (class "Default")
      (node (ref "DA2") (pin "D7") (pinfunction "PD7(I/O,FT)_D7") (pintype "passive"))
    )
    (net (code "125") (name "unconnected-(DA2A-PD8(I{slash}O,FT)-PadH2)") (class "Default")
      (node (ref "DA2") (pin "H2") (pinfunction "PD8(I/O,FT)_H2") (pintype "passive"))
    )
    (net (code "126") (name "unconnected-(DA2A-PD9(I{slash}O,FT)-PadH1)") (class "Default")
      (node (ref "DA2") (pin "H1") (pinfunction "PD9(I/O,FT)_H1") (pintype "passive"))
    )
    (net (code "127") (name "unconnected-(DA2A-PD10(I{slash}O,FT)-PadG5)") (class "Default")
      (node (ref "DA2") (pin "G5") (pinfunction "PD10(I/O,FT)_G5") (pintype "passive"))
    )
    (net (code "128") (name "unconnected-(DA2A-PD11(I{slash}O,FT)-PadG4)") (class "Default")
      (node (ref "DA2") (pin "G4") (pinfunction "PD11(I/O,FT)_G4") (pintype "passive"))
    )
    (net (code "129") (name "unconnected-(DA2A-PD12(I{slash}O,FT_fl)-PadF4)") (class "Default")
      (node (ref "DA2") (pin "F4") (pinfunction "PD12(I/O,FT_fl)_F4") (pintype "passive"))
    )
    (net (code "130") (name "unconnected-(DA2A-PD13(I{slash}O,FT_fl)-PadG3)") (class "Default")
      (node (ref "DA2") (pin "G3") (pinfunction "PD13(I/O,FT_fl)_G3") (pintype "passive"))
    )
    (net (code "131") (name "unconnected-(DA2A-PD14(I{slash}O,FT)-PadF3)") (class "Default")
      (node (ref "DA2") (pin "F3") (pinfunction "PD14(I/O,FT)_F3") (pintype "passive"))
    )
    (net (code "132") (name "unconnected-(DA2A-PD15(I{slash}O,FT)-PadF1)") (class "Default")
      (node (ref "DA2") (pin "F1") (pinfunction "PD15(I/O,FT)_F1") (pintype "passive"))
    )
    (net (code "133") (name "unconnected-(DA2A-PE0(I{slash}O,FT)-PadA10)") (class "Default")
      (node (ref "DA2") (pin "A10") (pinfunction "PE0(I/O,FT)_A10") (pintype "passive"))
    )
    (net (code "134") (name "unconnected-(DA2A-PE1(I{slash}O,FT)-PadA11)") (class "Default")
      (node (ref "DA2") (pin "A11") (pinfunction "PE1(I/O,FT)_A11") (pintype "passive"))
    )
    (net (code "135") (name "unconnected-(DA2A-PE2(I{slash}O,FT_I)-PadB11)") (class "Default")
      (node (ref "DA2") (pin "B11") (pinfunction "PE2(I/O,FT_I)_B11") (pintype "passive"))
    )
    (net (code "136") (name "unconnected-(DA2A-PE3(I{slash}O,FT_I)-PadC11)") (class "Default")
      (node (ref "DA2") (pin "C11") (pinfunction "PE3(I/O,FT_I)_C11") (pintype "passive"))
    )
    (net (code "137") (name "unconnected-(DA2A-PE7(I{slash}O,FT)-PadM6)") (class "Default")
      (node (ref "DA2") (pin "M6") (pinfunction "PE7(I/O,FT)_M6") (pintype "passive"))
    )
    (net (code "138") (name "unconnected-(DA2A-PE8(I{slash}O,FT)-PadH6)") (class "Default")
      (node (ref "DA2") (pin "H6") (pinfunction "PE8(I/O,FT)_H6") (pintype "passive"))
    )
    (net (code "139") (name "unconnected-(DA2A-PE9(I{slash}O,FT)-PadG6)") (class "Default")
      (node (ref "DA2") (pin "G6") (pinfunction "PE9(I/O,FT)_G6") (pintype "passive"))
    )
    (net (code "140") (name "unconnected-(DA2A-PE10(I{slash}O,FT)-PadK5)") (class "Default")
      (node (ref "DA2") (pin "K5") (pinfunction "PE10(I/O,FT)_K5") (pintype "passive"))
    )
    (net (code "141") (name "unconnected-(DA2A-PE11(I{slash}O,FT)-PadL5)") (class "Default")
      (node (ref "DA2") (pin "L5") (pinfunction "PE11(I/O,FT)_L5") (pintype "passive"))
    )
    (net (code "142") (name "unconnected-(DA2A-PE12(I{slash}O,FT)-PadM5)") (class "Default")
      (node (ref "DA2") (pin "M5") (pinfunction "PE12(I/O,FT)_M5") (pintype "passive"))
    )
    (net (code "143") (name "unconnected-(DA2A-PE13(I{slash}O,FT)-PadJ5)") (class "Default")
      (node (ref "DA2") (pin "J5") (pinfunction "PE13(I/O,FT)_J5") (pintype "passive"))
    )
    (net (code "144") (name "unconnected-(DA2A-PE14(I{slash}O,FT)-PadH5)") (class "Default")
      (node (ref "DA2") (pin "H5") (pinfunction "PE14(I/O,FT)_H5") (pintype "passive"))
    )
    (net (code "145") (name "unconnected-(DA2A-PE15(I{slash}O,FT)-PadK4)") (class "Default")
      (node (ref "DA2") (pin "K4") (pinfunction "PE15(I/O,FT)_K4") (pintype "passive"))
    )
    (net (code "146") (name "unconnected-(DA2A-PF13(I{slash}O,FT)-PadM7)") (class "Default")
      (node (ref "DA2") (pin "M7") (pinfunction "PF13(I/O,FT)_M7") (pintype "passive"))
    )
    (net (code "147") (name "unconnected-(DA2A-PF14(I{slash}O,FT_f)-PadG7)") (class "Default")
      (node (ref "DA2") (pin "G7") (pinfunction "PF14(I/O,FT_f)_G7") (pintype "passive"))
    )
    (net (code "148") (name "unconnected-(DA2A-PF15(I{slash}O,FT_f)-PadJ6)") (class "Default")
      (node (ref "DA2") (pin "J6") (pinfunction "PF15(I/O,FT_f)_J6") (pintype "passive"))
    )
    (net (code "149") (name "unconnected-(DA2A-PG2(I{slash}O,FT_s)-PadF2)") (class "Default")
      (node (ref "DA2") (pin "F2") (pinfunction "PG2(I/O,FT_s)_F2") (pintype "passive"))
    )
    (net (code "150") (name "unconnected-(DA2A-PG3(I{slash}O,FT_s)-PadF5)") (class "Default")
      (node (ref "DA2") (pin "F5") (pinfunction "PG3(I/O,FT_s)_F5") (pintype "passive"))
    )
    (net (code "151") (name "unconnected-(DA2A-PG4(I{slash}O,FT_s)-PadF6)") (class "Default")
      (node (ref "DA2") (pin "F6") (pinfunction "PG4(I/O,FT_s)_F6") (pintype "passive"))
    )
    (net (code "152") (name "unconnected-(DA2A-PG5(I{slash}O,FT_s)-PadF7)") (class "Default")
      (node (ref "DA2") (pin "F7") (pinfunction "PG5(I/O,FT_s)_F7") (pintype "passive"))
    )
    (net (code "153") (name "unconnected-(DA2A-PG6(I{slash}O,FT_s)-PadE5)") (class "Default")
      (node (ref "DA2") (pin "E5") (pinfunction "PG6(I/O,FT_s)_E5") (pintype "passive"))
    )
    (net (code "154") (name "unconnected-(DA2A-PG9(I{slash}O,FT_s)-PadC7)") (class "Default")
      (node (ref "DA2") (pin "C7") (pinfunction "PG9(I/O,FT_s)_C7") (pintype "passive"))
    )
    (net (code "155") (name "unconnected-(DA2A-PG10(I{slash}O,FT_s)-PadB7)") (class "Default")
      (node (ref "DA2") (pin "B7") (pinfunction "PG10(I/O,FT_s)_B7") (pintype "passive"))
    )
    (net (code "156") (name "unconnected-(DA2A-PG13(I{slash}O,FT_fs)-PadD8)") (class "Default")
      (node (ref "DA2") (pin "D8") (pinfunction "PG13(I/O,FT_fs)_D8") (pintype "passive"))
    )
    (net (code "157") (name "unconnected-(DA2A-PH3{slash}BOOT0(I{slash}O,FT)-PadB9)") (class "Default")
      (node (ref "DA2") (pin "B9") (pinfunction "PH3/BOOT0(I/O,FT)_B9") (pintype "passive"))
    )
    (net (code "158") (name "unconnected-(DA3-CTRL-PadC4)") (class "Default")
      (node (ref "DA3") (pin "C4") (pinfunction "CTRL_C4") (pintype "passive"))
    )
    (net (code "159") (name "unconnected-(DA3-LOAD-PadD4)") (class "Default")
      (node (ref "DA3") (pin "D4") (pinfunction "LOAD_D4") (pintype "passive"))
    )
  )
)
